# MC33079DG_Breakout.net
KiCad netlist of a schematic drawn in EAGLE
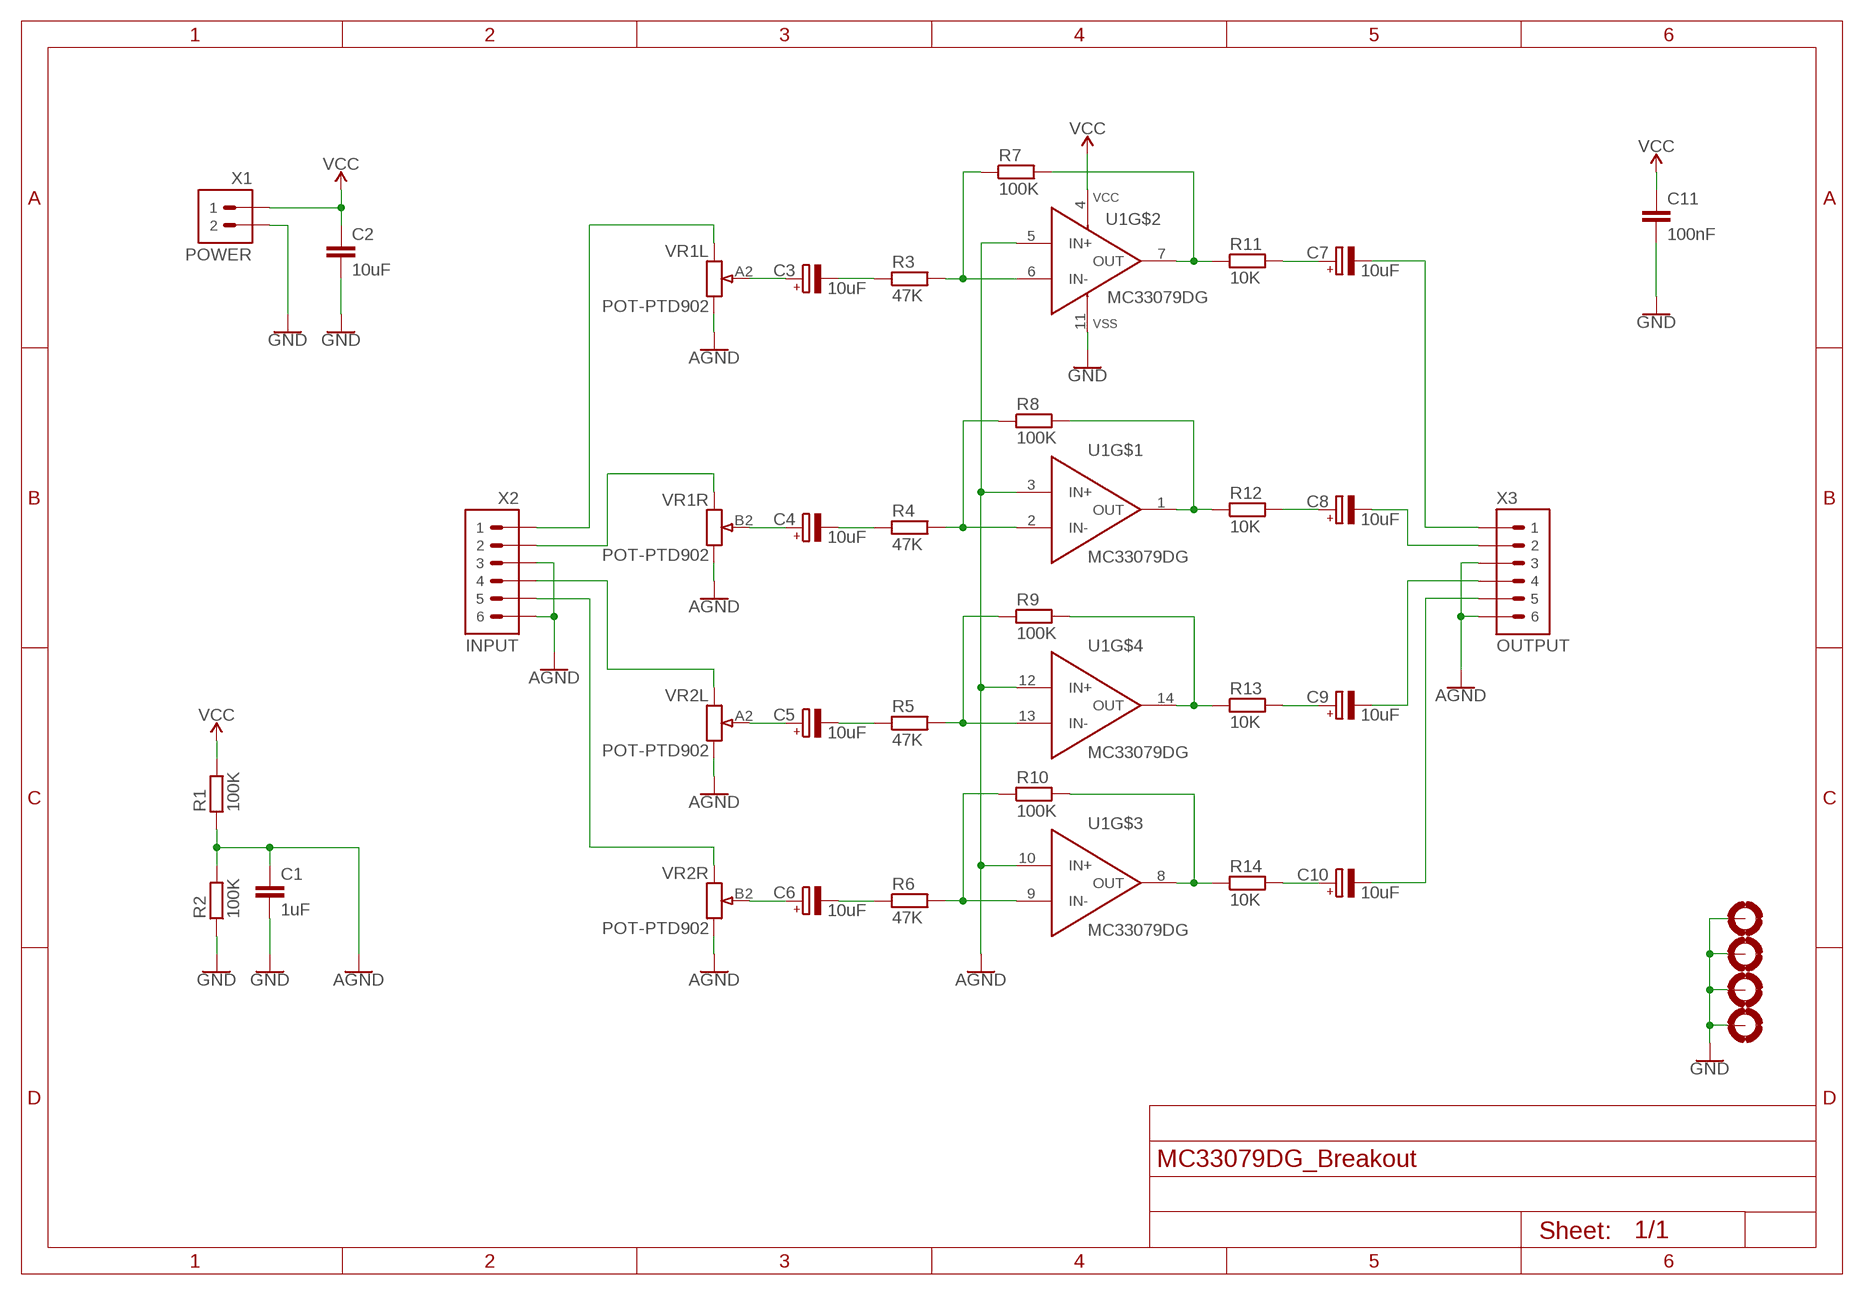
[diagram p0: schematic, sheet 1]

(export (version "E")
  (design (tool "Eeschema 10.0.6"))
  (components
    (comp (ref "C1")
      (value "1uF")
      (footprint "eagle-import:C0603")
      (libsource (lib "eagle-import") (part "CAPC0603"))
    )
    (comp (ref "C2")
      (value "10uF")
      (footprint "eagle-import:C0603")
      (libsource (lib "eagle-import") (part "CAPC0603"))
    )
    (comp (ref "C3")
      (value "10uF")
      (footprint "eagle-import:ROQANG-RVT0405")
      (libsource (lib "eagle-import") (part "CAP-POL-ALUMROQANG-RVT0405"))
    )
    (comp (ref "C4")
      (value "10uF")
      (footprint "eagle-import:ROQANG-RVT0405")
      (libsource (lib "eagle-import") (part "CAP-POL-ALUMROQANG-RVT0405"))
    )
    (comp (ref "C5")
      (value "10uF")
      (footprint "eagle-import:ROQANG-RVT0405")
      (libsource (lib "eagle-import") (part "CAP-POL-ALUMROQANG-RVT0405"))
    )
    (comp (ref "C6")
      (value "10uF")
      (footprint "eagle-import:ROQANG-RVT0405")
      (libsource (lib "eagle-import") (part "CAP-POL-ALUMROQANG-RVT0405"))
    )
    (comp (ref "C7")
      (value "10uF")
      (footprint "eagle-import:ROQANG-RVT0405")
      (libsource (lib "eagle-import") (part "CAP-POL-ALUMROQANG-RVT0405"))
    )
    (comp (ref "C8")
      (value "10uF")
      (footprint "eagle-import:ROQANG-RVT0405")
      (libsource (lib "eagle-import") (part "CAP-POL-ALUMROQANG-RVT0405"))
    )
    (comp (ref "C9")
      (value "10uF")
      (footprint "eagle-import:ROQANG-RVT0405")
      (libsource (lib "eagle-import") (part "CAP-POL-ALUMROQANG-RVT0405"))
    )
    (comp (ref "C10")
      (value "10uF")
      (footprint "eagle-import:ROQANG-RVT0405")
      (libsource (lib "eagle-import") (part "CAP-POL-ALUMROQANG-RVT0405"))
    )
    (comp (ref "C11")
      (value "100nF")
      (footprint "eagle-import:C0603")
      (libsource (lib "eagle-import") (part "CAPC0603"))
    )
    (comp (ref "H1")
      (value "MOUNTHOLE-PAD3.2")
      (footprint "eagle-import:3.2-PAD")
      (libsource (lib "eagle-import") (part "MOUNTHOLE-PAD3.2"))
    )
    (comp (ref "H2")
      (value "MOUNTHOLE-PAD3.2")
      (footprint "eagle-import:3.2-PAD")
      (libsource (lib "eagle-import") (part "MOUNTHOLE-PAD3.2"))
    )
    (comp (ref "H3")
      (value "MOUNTHOLE-PAD3.2")
      (footprint "eagle-import:3.2-PAD")
      (libsource (lib "eagle-import") (part "MOUNTHOLE-PAD3.2"))
    )
    (comp (ref "H4")
      (value "MOUNTHOLE-PAD3.2")
      (footprint "eagle-import:3.2-PAD")
      (libsource (lib "eagle-import") (part "MOUNTHOLE-PAD3.2"))
    )
    (comp (ref "R1")
      (value "100K")
      (footprint "eagle-import:R0603")
      (libsource (lib "eagle-import") (part "RESISTOR0603"))
    )
    (comp (ref "R2")
      (value "100K")
      (footprint "eagle-import:R0603")
      (libsource (lib "eagle-import") (part "RESISTOR0603"))
    )
    (comp (ref "R3")
      (value "47K")
      (footprint "eagle-import:R0603")
      (libsource (lib "eagle-import") (part "RESISTOR0603"))
    )
    (comp (ref "R4")
      (value "47K")
      (footprint "eagle-import:R0603")
      (libsource (lib "eagle-import") (part "RESISTOR0603"))
    )
    (comp (ref "R5")
      (value "47K")
      (footprint "eagle-import:R0603")
      (libsource (lib "eagle-import") (part "RESISTOR0603"))
    )
    (comp (ref "R6")
      (value "47K")
      (footprint "eagle-import:R0603")
      (libsource (lib "eagle-import") (part "RESISTOR0603"))
    )
    (comp (ref "R7")
      (value "100K")
      (footprint "eagle-import:R0603")
      (libsource (lib "eagle-import") (part "RESISTOR0603"))
    )
    (comp (ref "R8")
      (value "100K")
      (footprint "eagle-import:R0603")
      (libsource (lib "eagle-import") (part "RESISTOR0603"))
    )
    (comp (ref "R9")
      (value "100K")
      (footprint "eagle-import:R0603")
      (libsource (lib "eagle-import") (part "RESISTOR0603"))
    )
    (comp (ref "R10")
      (value "100K")
      (footprint "eagle-import:R0603")
      (libsource (lib "eagle-import") (part "RESISTOR0603"))
    )
    (comp (ref "R11")
      (value "10K")
      (footprint "eagle-import:R0603")
      (libsource (lib "eagle-import") (part "RESISTOR0603"))
    )
    (comp (ref "R12")
      (value "10K")
      (footprint "eagle-import:R0603")
      (libsource (lib "eagle-import") (part "RESISTOR0603"))
    )
    (comp (ref "R13")
      (value "10K")
      (footprint "eagle-import:R0603")
      (libsource (lib "eagle-import") (part "RESISTOR0603"))
    )
    (comp (ref "R14")
      (value "10K")
      (footprint "eagle-import:R0603")
      (libsource (lib "eagle-import") (part "RESISTOR0603"))
    )
    (comp (ref "U1")
      (value "MC33079DG")
      (footprint "eagle-import:SOIC-14")
      (libsource (lib "eagle-import") (part "OPAMP-MC33079DG"))
    )
    (comp (ref "VR1")
      (value "POT-PTD902")
      (footprint "eagle-import:POT-PTD902")
      (libsource (lib "eagle-import") (part "POT-PTD902"))
    )
    (comp (ref "VR2")
      (value "POT-PTD902")
      (footprint "eagle-import:POT-PTD902")
      (libsource (lib "eagle-import") (part "POT-PTD902"))
    )
    (comp (ref "X1")
      (value "POWER")
      (footprint "eagle-import:1X02P-2.54")
      (libsource (lib "eagle-import") (part "HEADER-1X02-2.54POL"))
    )
    (comp (ref "X2")
      (value "INPUT")
      (footprint "eagle-import:1X06-2.54")
      (libsource (lib "eagle-import") (part "HEADER-1X06-2.54"))
    )
    (comp (ref "X3")
      (value "OUTPUT")
      (footprint "eagle-import:1X06-2.54")
      (libsource (lib "eagle-import") (part "HEADER-1X06-2.54"))
    )
  )
  (nets
    (net (code "1") (name "AGND") (class "Default")
      (node (ref "C1") (pin "1") (pinfunction "1_1") (pintype "passive"))
      (node (ref "R1") (pin "1") (pinfunction "1_1") (pintype "passive"))
      (node (ref "R2") (pin "2") (pinfunction "2_2") (pintype "passive"))
      (node (ref "U1") (pin "10") (pinfunction "IN+_10") (pintype "bidirectional"))
      (node (ref "U1") (pin "12") (pinfunction "IN+_12") (pintype "bidirectional"))
      (node (ref "U1") (pin "3") (pinfunction "IN+_3") (pintype "bidirectional"))
      (node (ref "U1") (pin "5") (pinfunction "IN+_5") (pintype "bidirectional"))
      (node (ref "VR1") (pin "A1") (pinfunction "1_A1") (pintype "bidirectional"))
      (node (ref "VR1") (pin "B1") (pinfunction "1_B1") (pintype "bidirectional"))
      (node (ref "VR2") (pin "A1") (pinfunction "1_A1") (pintype "bidirectional"))
      (node (ref "VR2") (pin "B1") (pinfunction "1_B1") (pintype "bidirectional"))
      (node (ref "X2") (pin "3") (pinfunction "3_3") (pintype "passive"))
      (node (ref "X2") (pin "6") (pinfunction "6_6") (pintype "passive"))
      (node (ref "X3") (pin "3") (pinfunction "3_3") (pintype "passive"))
      (node (ref "X3") (pin "6") (pinfunction "6_6") (pintype "passive"))
    )
    (net (code "2") (name "GND") (class "Default")
      (node (ref "C1") (pin "2") (pinfunction "2_2") (pintype "passive"))
      (node (ref "C11") (pin "2") (pinfunction "2_2") (pintype "passive"))
      (node (ref "C2") (pin "2") (pinfunction "2_2") (pintype "passive"))
      (node (ref "H1") (pin "B3,2") (pinfunction "MOUNT_B3,2") (pintype "passive"))
      (node (ref "H2") (pin "B3,2") (pinfunction "MOUNT_B3,2") (pintype "passive"))
      (node (ref "H3") (pin "B3,2") (pinfunction "MOUNT_B3,2") (pintype "passive"))
      (node (ref "H4") (pin "B3,2") (pinfunction "MOUNT_B3,2") (pintype "passive"))
      (node (ref "R2") (pin "1") (pinfunction "1_1") (pintype "passive"))
      (node (ref "U1") (pin "11") (pinfunction "VSS_11") (pintype "bidirectional"))
      (node (ref "X1") (pin "2") (pinfunction "2_2") (pintype "passive"))
    )
    (net (code "3") (name "Net-(C3-Pad-)") (class "Default")
      (node (ref "C3") (pin "-") (pinfunction "-_-") (pintype "passive"))
      (node (ref "R3") (pin "1") (pinfunction "1_1") (pintype "passive"))
    )
    (net (code "4") (name "Net-(C4-Pad-)") (class "Default")
      (node (ref "C4") (pin "-") (pinfunction "-_-") (pintype "passive"))
      (node (ref "R4") (pin "1") (pinfunction "1_1") (pintype "passive"))
    )
    (net (code "5") (name "Net-(C5-Pad-)") (class "Default")
      (node (ref "C5") (pin "-") (pinfunction "-_-") (pintype "passive"))
      (node (ref "R5") (pin "1") (pinfunction "1_1") (pintype "passive"))
    )
    (net (code "6") (name "Net-(C6-Pad-)") (class "Default")
      (node (ref "C6") (pin "-") (pinfunction "-_-") (pintype "passive"))
      (node (ref "R6") (pin "1") (pinfunction "1_1") (pintype "passive"))
    )
    (net (code "7") (name "Net-(C7-Pad+)") (class "Default")
      (node (ref "C7") (pin "+") (pinfunction "+_+") (pintype "passive"))
      (node (ref "R11") (pin "2") (pinfunction "2_2") (pintype "passive"))
    )
    (net (code "8") (name "Net-(C7-Pad-)") (class "Default")
      (node (ref "C7") (pin "-") (pinfunction "-_-") (pintype "passive"))
      (node (ref "X3") (pin "1") (pinfunction "1_1") (pintype "passive"))
    )
    (net (code "9") (name "Net-(C8-Pad+)") (class "Default")
      (node (ref "C8") (pin "+") (pinfunction "+_+") (pintype "passive"))
      (node (ref "R12") (pin "2") (pinfunction "2_2") (pintype "passive"))
    )
    (net (code "10") (name "Net-(C8-Pad-)") (class "Default")
      (node (ref "C8") (pin "-") (pinfunction "-_-") (pintype "passive"))
      (node (ref "X3") (pin "2") (pinfunction "2_2") (pintype "passive"))
    )
    (net (code "11") (name "Net-(C9-Pad+)") (class "Default")
      (node (ref "C9") (pin "+") (pinfunction "+_+") (pintype "passive"))
      (node (ref "R13") (pin "2") (pinfunction "2_2") (pintype "passive"))
    )
    (net (code "12") (name "Net-(C9-Pad-)") (class "Default")
      (node (ref "C9") (pin "-") (pinfunction "-_-") (pintype "passive"))
      (node (ref "X3") (pin "4") (pinfunction "4_4") (pintype "passive"))
    )
    (net (code "13") (name "Net-(C10-Pad+)") (class "Default")
      (node (ref "C10") (pin "+") (pinfunction "+_+") (pintype "passive"))
      (node (ref "R14") (pin "2") (pinfunction "2_2") (pintype "passive"))
    )
    (net (code "14") (name "Net-(C10-Pad-)") (class "Default")
      (node (ref "C10") (pin "-") (pinfunction "-_-") (pintype "passive"))
      (node (ref "X3") (pin "5") (pinfunction "5_5") (pintype "passive"))
    )
    (net (code "15") (name "Net-(U1A-IN-)") (class "Default")
      (node (ref "R4") (pin "2") (pinfunction "2_2") (pintype "passive"))
      (node (ref "R8") (pin "1") (pinfunction "1_1") (pintype "passive"))
      (node (ref "U1") (pin "2") (pinfunction "IN-_2") (pintype "bidirectional"))
    )
    (net (code "16") (name "Net-(U1A-OUT)") (class "Default")
      (node (ref "R12") (pin "1") (pinfunction "1_1") (pintype "passive"))
      (node (ref "R8") (pin "2") (pinfunction "2_2") (pintype "passive"))
      (node (ref "U1") (pin "1") (pinfunction "OUT_1") (pintype "bidirectional"))
    )
    (net (code "17") (name "Net-(U1B-IN-)") (class "Default")
      (node (ref "R3") (pin "2") (pinfunction "2_2") (pintype "passive"))
      (node (ref "R7") (pin "1") (pinfunction "1_1") (pintype "passive"))
      (node (ref "U1") (pin "6") (pinfunction "IN-_6") (pintype "bidirectional"))
    )
    (net (code "18") (name "Net-(U1B-OUT)") (class "Default")
      (node (ref "R11") (pin "1") (pinfunction "1_1") (pintype "passive"))
      (node (ref "R7") (pin "2") (pinfunction "2_2") (pintype "passive"))
      (node (ref "U1") (pin "7") (pinfunction "OUT_7") (pintype "bidirectional"))
    )
    (net (code "19") (name "Net-(U1C-IN-)") (class "Default")
      (node (ref "R10") (pin "1") (pinfunction "1_1") (pintype "passive"))
      (node (ref "R6") (pin "2") (pinfunction "2_2") (pintype "passive"))
      (node (ref "U1") (pin "9") (pinfunction "IN-_9") (pintype "bidirectional"))
    )
    (net (code "20") (name "Net-(U1C-OUT)") (class "Default")
      (node (ref "R10") (pin "2") (pinfunction "2_2") (pintype "passive"))
      (node (ref "R14") (pin "1") (pinfunction "1_1") (pintype "passive"))
      (node (ref "U1") (pin "8") (pinfunction "OUT_8") (pintype "bidirectional"))
    )
    (net (code "21") (name "Net-(U1D-IN-)") (class "Default")
      (node (ref "R5") (pin "2") (pinfunction "2_2") (pintype "passive"))
      (node (ref "R9") (pin "1") (pinfunction "1_1") (pintype "passive"))
      (node (ref "U1") (pin "13") (pinfunction "IN-_13") (pintype "bidirectional"))
    )
    (net (code "22") (name "Net-(U1D-OUT)") (class "Default")
      (node (ref "R13") (pin "1") (pinfunction "1_1") (pintype "passive"))
      (node (ref "R9") (pin "2") (pinfunction "2_2") (pintype "passive"))
      (node (ref "U1") (pin "14") (pinfunction "OUT_14") (pintype "bidirectional"))
    )
    (net (code "23") (name "Net-(VR1A-2)") (class "Default")
      (node (ref "C3") (pin "+") (pinfunction "+_+") (pintype "passive"))
      (node (ref "VR1") (pin "A2") (pinfunction "2_A2") (pintype "bidirectional"))
    )
    (net (code "24") (name "Net-(VR1A-3)") (class "Default")
      (node (ref "VR1") (pin "A3") (pinfunction "3_A3") (pintype "bidirectional"))
      (node (ref "X2") (pin "1") (pinfunction "1_1") (pintype "passive"))
    )
    (net (code "25") (name "Net-(VR1B-2)") (class "Default")
      (node (ref "C4") (pin "+") (pinfunction "+_+") (pintype "passive"))
      (node (ref "VR1") (pin "B2") (pinfunction "2_B2") (pintype "bidirectional"))
    )
    (net (code "26") (name "Net-(VR1B-3)") (class "Default")
      (node (ref "VR1") (pin "B3") (pinfunction "3_B3") (pintype "bidirectional"))
      (node (ref "X2") (pin "2") (pinfunction "2_2") (pintype "passive"))
    )
    (net (code "27") (name "Net-(VR2A-2)") (class "Default")
      (node (ref "C5") (pin "+") (pinfunction "+_+") (pintype "passive"))
      (node (ref "VR2") (pin "A2") (pinfunction "2_A2") (pintype "bidirectional"))
    )
    (net (code "28") (name "Net-(VR2A-3)") (class "Default")
      (node (ref "VR2") (pin "A3") (pinfunction "3_A3") (pintype "bidirectional"))
      (node (ref "X2") (pin "4") (pinfunction "4_4") (pintype "passive"))
    )
    (net (code "29") (name "Net-(VR2B-2)") (class "Default")
      (node (ref "C6") (pin "+") (pinfunction "+_+") (pintype "passive"))
      (node (ref "VR2") (pin "B2") (pinfunction "2_B2") (pintype "bidirectional"))
    )
    (net (code "30") (name "Net-(VR2B-3)") (class "Default")
      (node (ref "VR2") (pin "B3") (pinfunction "3_B3") (pintype "bidirectional"))
      (node (ref "X2") (pin "5") (pinfunction "5_5") (pintype "passive"))
    )
    (net (code "31") (name "VCC") (class "Default")
      (node (ref "C11") (pin "1") (pinfunction "1_1") (pintype "passive"))
      (node (ref "C2") (pin "1") (pinfunction "1_1") (pintype "passive"))
      (node (ref "R1") (pin "2") (pinfunction "2_2") (pintype "passive"))
      (node (ref "U1") (pin "4") (pinfunction "VCC_4") (pintype "bidirectional"))
      (node (ref "X1") (pin "1") (pinfunction "1_1") (pintype "passive"))
    )
  )
)
